# v0_6.net
KiCad netlist of a schematic drawn in EAGLE
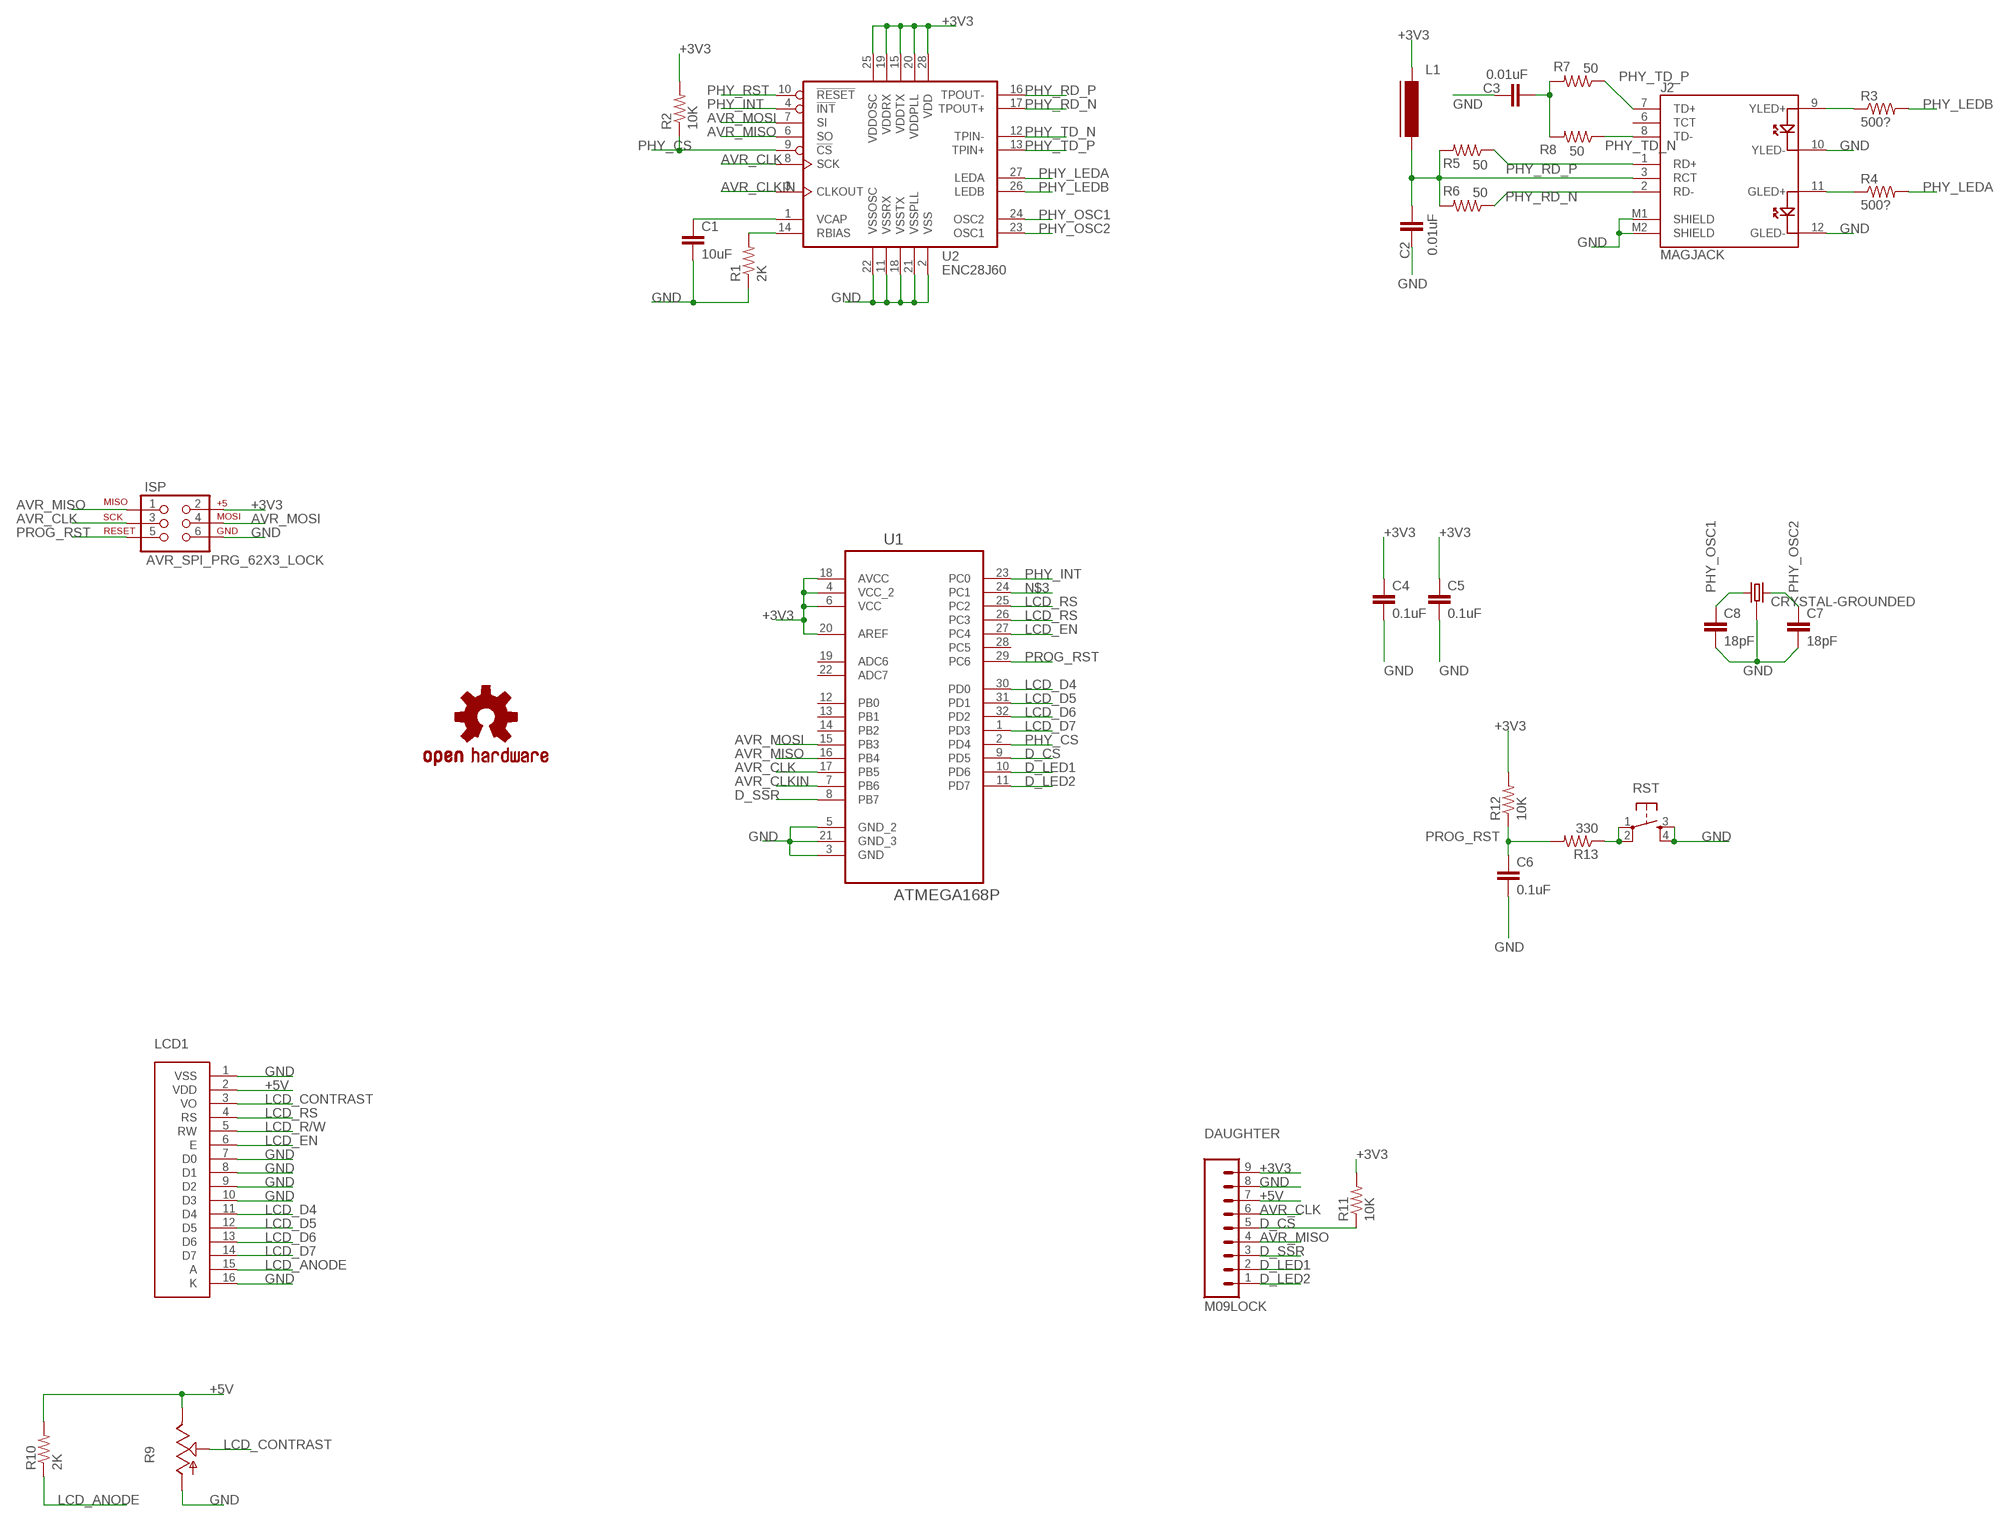
[diagram p0: schematic, sheet 1]

(export (version "E")
  (design (tool "Eeschema 10.0.6"))
  (components
    (comp (ref "C1")
      (value "10uF")
      (footprint "eagle-import:0603-CAP")
      (libsource (lib "eagle-import") (part "10UF-6.3V-20%(0603)"))
    )
    (comp (ref "C2")
      (value "0.01uF")
      (footprint "eagle-import:0603-CAP")
      (libsource (lib "eagle-import") (part "CAP0603-CAP"))
    )
    (comp (ref "C3")
      (value "0.01uF")
      (footprint "eagle-import:0603-CAP")
      (libsource (lib "eagle-import") (part "CAP0603-CAP"))
    )
    (comp (ref "C4")
      (value "0.1uF")
      (footprint "eagle-import:0402-CAP")
      (libsource (lib "eagle-import") (part "CAP0402-CAP"))
    )
    (comp (ref "C5")
      (value "0.1uF")
      (footprint "eagle-import:0402-CAP")
      (libsource (lib "eagle-import") (part "CAP0402-CAP"))
    )
    (comp (ref "C6")
      (value "0.1uF")
      (footprint "eagle-import:0603-CAP")
      (libsource (lib "eagle-import") (part "CAP0603-CAP"))
    )
    (comp (ref "C7")
      (value "18pF")
      (footprint "eagle-import:0402-CAP")
      (libsource (lib "eagle-import") (part "CAP0402-CAP"))
    )
    (comp (ref "C8")
      (value "18pF")
      (footprint "eagle-import:0402-CAP")
      (libsource (lib "eagle-import") (part "CAP0402-CAP"))
    )
    (comp (ref "DAUGHTER")
      (value "M09LOCK")
      (footprint "eagle-import:1X09_LOCK")
      (libsource (lib "eagle-import") (part "M09LOCK"))
    )
    (comp (ref "ISP")
      (value "AVR_SPI_PRG_62X3_LOCK")
      (footprint "eagle-import:2X3_LOCK")
      (libsource (lib "eagle-import") (part "AVR_SPI_PRG_62X3_LOCK"))
    )
    (comp (ref "J2")
      (value "MAGJACK")
      (footprint "eagle-import:MAGJACK")
      (libsource (lib "eagle-import") (part "MAGJACK"))
    )
    (comp (ref "L1")
      (value "FERRITE-0603")
      (footprint "eagle-import:FB603")
      (libsource (lib "eagle-import") (part "FERRITE-0603"))
    )
    (comp (ref "LCD1")
      (value "HD44780")
      (footprint "eagle-import:.1_16PIN")
      (libsource (lib "eagle-import") (part "HD44780"))
    )
    (comp (ref "LOGO1")
      (value "OSHW-LOGOS")
      (footprint "eagle-import:OSHW-LOGO-S")
      (libsource (lib "eagle-import") (part "OSHW-LOGOS"))
    )
    (comp (ref "R1")
      (value "2K")
      (footprint "eagle-import:0603-RES")
      (libsource (lib "eagle-import") (part "RESISTOR0603-RES"))
    )
    (comp (ref "R2")
      (value "10K")
      (footprint "eagle-import:0603-RES")
      (libsource (lib "eagle-import") (part "RESISTOR0603-RES"))
    )
    (comp (ref "R3")
      (value "500?")
      (footprint "eagle-import:0603-RES")
      (libsource (lib "eagle-import") (part "RESISTOR0603-RES"))
    )
    (comp (ref "R4")
      (value "500?")
      (footprint "eagle-import:0603-RES")
      (libsource (lib "eagle-import") (part "RESISTOR0603-RES"))
    )
    (comp (ref "R5")
      (value "50")
      (footprint "eagle-import:0603-RES")
      (libsource (lib "eagle-import") (part "RESISTOR0603-RES"))
    )
    (comp (ref "R6")
      (value "50")
      (footprint "eagle-import:0603-RES")
      (libsource (lib "eagle-import") (part "RESISTOR0603-RES"))
    )
    (comp (ref "R7")
      (value "50")
      (footprint "eagle-import:0603-RES")
      (libsource (lib "eagle-import") (part "RESISTOR0603-RES"))
    )
    (comp (ref "R8")
      (value "50")
      (footprint "eagle-import:0603-RES")
      (libsource (lib "eagle-import") (part "RESISTOR0603-RES"))
    )
    (comp (ref "R9")
      (value "TRIM_US-B64Y")
      (footprint "eagle-import:B64Y")
      (libsource (lib "eagle-import") (part "TRIM_US-B64Y"))
    )
    (comp (ref "R10")
      (value "2K")
      (footprint "eagle-import:0603-RES")
      (libsource (lib "eagle-import") (part "RESISTOR0603-RES"))
    )
    (comp (ref "R11")
      (value "10K")
      (footprint "eagle-import:0603-RES")
      (libsource (lib "eagle-import") (part "RESISTOR0603-RES"))
    )
    (comp (ref "R12")
      (value "10K")
      (footprint "eagle-import:0603-RES")
      (libsource (lib "eagle-import") (part "RESISTOR0603-RES"))
    )
    (comp (ref "R13")
      (value "330")
      (footprint "eagle-import:0603-RES")
      (libsource (lib "eagle-import") (part "RESISTOR0603-RES"))
    )
    (comp (ref "RST")
      (value "TAC_SWITCHSMD")
      (footprint "eagle-import:TACTILE-SWITCH-SMD")
      (libsource (lib "eagle-import") (part "TAC_SWITCHSMD"))
    )
    (comp (ref "U1")
      (value "ATMEGA168P")
      (footprint "eagle-import:QFP80P900X900X120-32N")
      (fields (field (name "MPN") "ATMEGA168P-20AU"))
      (libsource (lib "eagle-import") (part "ATMEGA168P-20AU"))
    )
    (comp (ref "U2")
      (value "ENC28J60")
      (footprint "eagle-import:SOIC-28W")
      (libsource (lib "eagle-import") (part "IC_ENC28J60-SOIC-28"))
    )
    (comp (ref "Y1")
      (value "CRYSTAL-GROUNDED")
      (footprint "eagle-import:CRYSTAL-SMD-5X3")
      (libsource (lib "eagle-import") (part "CRYSTAL-GROUNDED"))
    )
  )
  (nets
    (net (code "1") (name "/+3V3") (class "Default")
      (node (ref "C4") (pin "1") (pinfunction "1_1") (pintype "passive"))
      (node (ref "C5") (pin "1") (pinfunction "1_1") (pintype "passive"))
      (node (ref "DAUGHTER") (pin "9") (pinfunction "9_9") (pintype "passive"))
      (node (ref "ISP") (pin "2") (pinfunction "2_2") (pintype "passive"))
      (node (ref "L1") (pin "1") (pinfunction "1_1") (pintype "passive"))
      (node (ref "R11") (pin "2") (pinfunction "2_2") (pintype "passive"))
      (node (ref "R12") (pin "2") (pinfunction "2_2") (pintype "passive"))
      (node (ref "R2") (pin "2") (pinfunction "2_2") (pintype "passive"))
      (node (ref "U1") (pin "18") (pinfunction "AVCC_18") (pintype "power_in"))
      (node (ref "U1") (pin "20") (pinfunction "AREF_20") (pintype "input"))
      (node (ref "U1") (pin "4") (pinfunction "VCC_2_4") (pintype "power_in"))
      (node (ref "U1") (pin "6") (pinfunction "VCC_6") (pintype "power_in"))
      (node (ref "U2") (pin "15") (pinfunction "VDDTX_15") (pintype "power_in"))
      (node (ref "U2") (pin "19") (pinfunction "VDDRX_19") (pintype "power_in"))
      (node (ref "U2") (pin "20") (pinfunction "VDDPLL_20") (pintype "power_in"))
      (node (ref "U2") (pin "25") (pinfunction "VDDOSC_25") (pintype "power_in"))
      (node (ref "U2") (pin "28") (pinfunction "VDD_28") (pintype "power_in"))
    )
    (net (code "2") (name "/+5V") (class "Default")
      (node (ref "DAUGHTER") (pin "7") (pinfunction "7_7") (pintype "passive"))
      (node (ref "LCD1") (pin "2") (pinfunction "VDD_2") (pintype "bidirectional"))
      (node (ref "R10") (pin "2") (pinfunction "2_2") (pintype "passive"))
      (node (ref "R9") (pin "E") (pinfunction "E_E") (pintype "passive"))
    )
    (net (code "3") (name "/AVR_CLK") (class "Default")
      (node (ref "DAUGHTER") (pin "6") (pinfunction "6_6") (pintype "passive"))
      (node (ref "ISP") (pin "3") (pinfunction "3_3") (pintype "passive"))
      (node (ref "U1") (pin "17") (pinfunction "PB5_17") (pintype "bidirectional"))
      (node (ref "U2") (pin "8") (pinfunction "SCK_8") (pintype "input"))
    )
    (net (code "4") (name "/AVR_CLKIN") (class "Default")
      (node (ref "U1") (pin "7") (pinfunction "PB6_7") (pintype "bidirectional"))
      (node (ref "U2") (pin "3") (pinfunction "CLKOUT_3") (pintype "output"))
    )
    (net (code "5") (name "/AVR_MISO") (class "Default")
      (node (ref "DAUGHTER") (pin "4") (pinfunction "4_4") (pintype "passive"))
      (node (ref "ISP") (pin "1") (pinfunction "1_1") (pintype "passive"))
      (node (ref "U1") (pin "16") (pinfunction "PB4_16") (pintype "bidirectional"))
      (node (ref "U2") (pin "6") (pinfunction "SO_6") (pintype "output"))
    )
    (net (code "6") (name "/AVR_MOSI") (class "Default")
      (node (ref "ISP") (pin "4") (pinfunction "4_4") (pintype "passive"))
      (node (ref "U1") (pin "15") (pinfunction "PB3_15") (pintype "bidirectional"))
      (node (ref "U2") (pin "7") (pinfunction "SI_7") (pintype "input"))
    )
    (net (code "7") (name "/D_CS") (class "Default")
      (node (ref "DAUGHTER") (pin "5") (pinfunction "5_5") (pintype "passive"))
      (node (ref "R11") (pin "1") (pinfunction "1_1") (pintype "passive"))
      (node (ref "U1") (pin "9") (pinfunction "PD5_9") (pintype "bidirectional"))
    )
    (net (code "8") (name "/D_LED1") (class "Default")
      (node (ref "DAUGHTER") (pin "2") (pinfunction "2_2") (pintype "passive"))
      (node (ref "U1") (pin "10") (pinfunction "PD6_10") (pintype "bidirectional"))
    )
    (net (code "9") (name "/D_LED2") (class "Default")
      (node (ref "DAUGHTER") (pin "1") (pinfunction "1_1") (pintype "passive"))
      (node (ref "U1") (pin "11") (pinfunction "PD7_11") (pintype "bidirectional"))
    )
    (net (code "10") (name "/D_SSR") (class "Default")
      (node (ref "DAUGHTER") (pin "3") (pinfunction "3_3") (pintype "passive"))
      (node (ref "U1") (pin "8") (pinfunction "PB7_8") (pintype "bidirectional"))
    )
    (net (code "11") (name "/GND") (class "Default")
      (node (ref "C1") (pin "2") (pinfunction "2_2") (pintype "passive"))
      (node (ref "C2") (pin "1") (pinfunction "1_1") (pintype "passive"))
      (node (ref "C3") (pin "1") (pinfunction "1_1") (pintype "passive"))
      (node (ref "C4") (pin "2") (pinfunction "2_2") (pintype "passive"))
      (node (ref "C5") (pin "2") (pinfunction "2_2") (pintype "passive"))
      (node (ref "C6") (pin "2") (pinfunction "2_2") (pintype "passive"))
      (node (ref "C7") (pin "2") (pinfunction "2_2") (pintype "passive"))
      (node (ref "C8") (pin "2") (pinfunction "2_2") (pintype "passive"))
      (node (ref "DAUGHTER") (pin "8") (pinfunction "8_8") (pintype "passive"))
      (node (ref "ISP") (pin "6") (pinfunction "6_6") (pintype "passive"))
      (node (ref "J2") (pin "10") (pinfunction "YLED-_10") (pintype "bidirectional"))
      (node (ref "J2") (pin "12") (pinfunction "GLED-_12") (pintype "bidirectional"))
      (node (ref "J2") (pin "M1") (pinfunction "SHIELD_M1") (pintype "bidirectional"))
      (node (ref "J2") (pin "M2") (pinfunction "SHIELD_M2") (pintype "bidirectional"))
      (node (ref "LCD1") (pin "1") (pinfunction "VSS_1") (pintype "bidirectional"))
      (node (ref "LCD1") (pin "10") (pinfunction "D3_10") (pintype "bidirectional"))
      (node (ref "LCD1") (pin "16") (pinfunction "K_16") (pintype "bidirectional"))
      (node (ref "LCD1") (pin "7") (pinfunction "D0_7") (pintype "bidirectional"))
      (node (ref "LCD1") (pin "8") (pinfunction "D1_8") (pintype "bidirectional"))
      (node (ref "LCD1") (pin "9") (pinfunction "D2_9") (pintype "bidirectional"))
      (node (ref "R1") (pin "1") (pinfunction "1_1") (pintype "passive"))
      (node (ref "R9") (pin "A") (pinfunction "A_A") (pintype "passive"))
      (node (ref "RST") (pin "3") (pinfunction "3_3") (pintype "passive"))
      (node (ref "RST") (pin "4") (pinfunction "4_4") (pintype "passive"))
      (node (ref "U1") (pin "21") (pinfunction "GND_3_21") (pintype "passive"))
      (node (ref "U1") (pin "3") (pinfunction "GND_3") (pintype "passive"))
      (node (ref "U1") (pin "5") (pinfunction "GND_2_5") (pintype "passive"))
      (node (ref "U2") (pin "11") (pinfunction "VSSRX_11") (pintype "power_in"))
      (node (ref "U2") (pin "18") (pinfunction "VSSTX_18") (pintype "power_in"))
      (node (ref "U2") (pin "2") (pinfunction "VSS_2") (pintype "power_in"))
      (node (ref "U2") (pin "21") (pinfunction "VSSPLL_21") (pintype "power_in"))
      (node (ref "U2") (pin "22") (pinfunction "VSSOSC_22") (pintype "power_in"))
      (node (ref "Y1") (pin "2") (pinfunction "3_2") (pintype "passive"))
      (node (ref "Y1") (pin "4") (pinfunction "3_4") (pintype "passive"))
    )
    (net (code "12") (name "/LCD_ANODE") (class "Default")
      (node (ref "LCD1") (pin "15") (pinfunction "A_15") (pintype "bidirectional"))
      (node (ref "R10") (pin "1") (pinfunction "1_1") (pintype "passive"))
    )
    (net (code "13") (name "/LCD_CONTRAST") (class "Default")
      (node (ref "LCD1") (pin "3") (pinfunction "VO_3") (pintype "bidirectional"))
      (node (ref "R9") (pin "S") (pinfunction "S_S") (pintype "passive"))
    )
    (net (code "14") (name "/LCD_D4") (class "Default")
      (node (ref "LCD1") (pin "11") (pinfunction "D4_11") (pintype "bidirectional"))
      (node (ref "U1") (pin "30") (pinfunction "PD0_30") (pintype "bidirectional"))
    )
    (net (code "15") (name "/LCD_D5") (class "Default")
      (node (ref "LCD1") (pin "12") (pinfunction "D5_12") (pintype "bidirectional"))
      (node (ref "U1") (pin "31") (pinfunction "PD1_31") (pintype "bidirectional"))
    )
    (net (code "16") (name "/LCD_D6") (class "Default")
      (node (ref "LCD1") (pin "13") (pinfunction "D6_13") (pintype "bidirectional"))
      (node (ref "U1") (pin "32") (pinfunction "PD2_32") (pintype "bidirectional"))
    )
    (net (code "17") (name "/LCD_D7") (class "Default")
      (node (ref "LCD1") (pin "14") (pinfunction "D7_14") (pintype "bidirectional"))
      (node (ref "U1") (pin "1") (pinfunction "PD3_1") (pintype "bidirectional"))
    )
    (net (code "18") (name "/LCD_EN") (class "Default")
      (node (ref "LCD1") (pin "6") (pinfunction "E_6") (pintype "bidirectional"))
      (node (ref "U1") (pin "27") (pinfunction "PC4_27") (pintype "bidirectional"))
    )
    (net (code "19") (name "/LCD_RS") (class "Default")
      (node (ref "LCD1") (pin "4") (pinfunction "RS_4") (pintype "bidirectional"))
      (node (ref "U1") (pin "25") (pinfunction "PC2_25") (pintype "bidirectional"))
    )
    (net (code "20") (name "/LCD_R{slash}W") (class "Default")
      (node (ref "LCD1") (pin "5") (pinfunction "RW_5") (pintype "bidirectional"))
      (node (ref "U1") (pin "26") (pinfunction "PC3_26") (pintype "bidirectional"))
    )
    (net (code "21") (name "/N$3") (class "Default")
      (node (ref "U1") (pin "24") (pinfunction "PC1_24") (pintype "bidirectional"))
    )
    (net (code "22") (name "/PHY_CS") (class "Default")
      (node (ref "R2") (pin "1") (pinfunction "1_1") (pintype "passive"))
      (node (ref "U1") (pin "2") (pinfunction "PD4_2") (pintype "bidirectional"))
      (node (ref "U2") (pin "9") (pinfunction "~{CS}_9") (pintype "input"))
    )
    (net (code "23") (name "/PHY_INT") (class "Default")
      (node (ref "U1") (pin "23") (pinfunction "PC0_23") (pintype "bidirectional"))
      (node (ref "U2") (pin "4") (pinfunction "~{INT}_4") (pintype "output"))
    )
    (net (code "24") (name "/PHY_LEDA") (class "Default")
      (node (ref "R4") (pin "2") (pinfunction "2_2") (pintype "passive"))
      (node (ref "U2") (pin "27") (pinfunction "LEDA_27") (pintype "output"))
    )
    (net (code "25") (name "/PHY_LEDB") (class "Default")
      (node (ref "R3") (pin "2") (pinfunction "2_2") (pintype "passive"))
      (node (ref "U2") (pin "26") (pinfunction "LEDB_26") (pintype "output"))
    )
    (net (code "26") (name "/PHY_OSC1") (class "Default")
      (node (ref "C8") (pin "1") (pinfunction "1_1") (pintype "passive"))
      (node (ref "U2") (pin "24") (pinfunction "OSC2_24") (pintype "output"))
      (node (ref "Y1") (pin "3") (pinfunction "1_3") (pintype "passive"))
    )
    (net (code "27") (name "/PHY_OSC2") (class "Default")
      (node (ref "C7") (pin "1") (pinfunction "1_1") (pintype "passive"))
      (node (ref "U2") (pin "23") (pinfunction "OSC1_23") (pintype "input"))
      (node (ref "Y1") (pin "1") (pinfunction "2_1") (pintype "passive"))
    )
    (net (code "28") (name "/PHY_RD_N") (class "Default")
      (node (ref "J2") (pin "2") (pinfunction "RD-_2") (pintype "bidirectional"))
      (node (ref "R6") (pin "1") (pinfunction "1_1") (pintype "passive"))
      (node (ref "U2") (pin "17") (pinfunction "TPOUT+_17") (pintype "output"))
    )
    (net (code "29") (name "/PHY_RD_P") (class "Default")
      (node (ref "J2") (pin "1") (pinfunction "RD+_1") (pintype "bidirectional"))
      (node (ref "R5") (pin "1") (pinfunction "1_1") (pintype "passive"))
      (node (ref "U2") (pin "16") (pinfunction "TPOUT-_16") (pintype "output"))
    )
    (net (code "30") (name "/PHY_RST") (class "Default")
      (node (ref "U2") (pin "10") (pinfunction "~{RESET}_10") (pintype "input"))
    )
    (net (code "31") (name "/PHY_TD_N") (class "Default")
      (node (ref "J2") (pin "8") (pinfunction "TD-_8") (pintype "bidirectional"))
      (node (ref "R8") (pin "1") (pinfunction "1_1") (pintype "passive"))
      (node (ref "U2") (pin "12") (pinfunction "TPIN-_12") (pintype "input"))
    )
    (net (code "32") (name "/PHY_TD_P") (class "Default")
      (node (ref "J2") (pin "7") (pinfunction "TD+_7") (pintype "bidirectional"))
      (node (ref "R7") (pin "1") (pinfunction "1_1") (pintype "passive"))
      (node (ref "U2") (pin "13") (pinfunction "TPIN+_13") (pintype "input"))
    )
    (net (code "33") (name "/PROG_RST") (class "Default")
      (node (ref "C6") (pin "1") (pinfunction "1_1") (pintype "passive"))
      (node (ref "ISP") (pin "5") (pinfunction "5_5") (pintype "passive"))
      (node (ref "R12") (pin "1") (pinfunction "1_1") (pintype "passive"))
      (node (ref "R13") (pin "2") (pinfunction "2_2") (pintype "passive"))
      (node (ref "U1") (pin "29") (pinfunction "PC6_29") (pintype "bidirectional"))
    )
    (net (code "34") (name "Net-(C3-Pad2)") (class "Default")
      (node (ref "C3") (pin "2") (pinfunction "2_2") (pintype "passive"))
      (node (ref "R7") (pin "2") (pinfunction "2_2") (pintype "passive"))
      (node (ref "R8") (pin "2") (pinfunction "2_2") (pintype "passive"))
    )
    (net (code "35") (name "Net-(J2-GLED+)") (class "Default")
      (node (ref "J2") (pin "11") (pinfunction "GLED+_11") (pintype "bidirectional"))
      (node (ref "R4") (pin "1") (pinfunction "1_1") (pintype "passive"))
    )
    (net (code "36") (name "Net-(J2-RCT)") (class "Default")
      (node (ref "C2") (pin "2") (pinfunction "2_2") (pintype "passive"))
      (node (ref "J2") (pin "3") (pinfunction "RCT_3") (pintype "bidirectional"))
      (node (ref "L1") (pin "2") (pinfunction "2_2") (pintype "passive"))
      (node (ref "R5") (pin "2") (pinfunction "2_2") (pintype "passive"))
      (node (ref "R6") (pin "2") (pinfunction "2_2") (pintype "passive"))
    )
    (net (code "37") (name "Net-(J2-YLED+)") (class "Default")
      (node (ref "J2") (pin "9") (pinfunction "YLED+_9") (pintype "bidirectional"))
      (node (ref "R3") (pin "1") (pinfunction "1_1") (pintype "passive"))
    )
    (net (code "38") (name "Net-(R13-Pad1)") (class "Default")
      (node (ref "R13") (pin "1") (pinfunction "1_1") (pintype "passive"))
      (node (ref "RST") (pin "1") (pinfunction "1_1") (pintype "passive"))
      (node (ref "RST") (pin "2") (pinfunction "2_2") (pintype "passive"))
    )
    (net (code "39") (name "Net-(U2-RBIAS)") (class "Default")
      (node (ref "R1") (pin "2") (pinfunction "2_2") (pintype "passive"))
      (node (ref "U2") (pin "14") (pinfunction "RBIAS_14") (pintype "input"))
    )
    (net (code "40") (name "Net-(U2-VCAP)") (class "Default")
      (node (ref "C1") (pin "1") (pinfunction "1_1") (pintype "passive"))
      (node (ref "U2") (pin "1") (pinfunction "VCAP_1") (pintype "input"))
    )
    (net (code "41") (name "unconnected-(J2-TCT-Pad6)") (class "Default")
      (node (ref "J2") (pin "6") (pinfunction "TCT_6") (pintype "bidirectional"))
    )
    (net (code "42") (name "unconnected-(U1-ADC6-Pad19)") (class "Default")
      (node (ref "U1") (pin "19") (pinfunction "ADC6_19") (pintype "input"))
    )
    (net (code "43") (name "unconnected-(U1-ADC7-Pad22)") (class "Default")
      (node (ref "U1") (pin "22") (pinfunction "ADC7_22") (pintype "input"))
    )
    (net (code "44") (name "unconnected-(U1-PB0-Pad12)") (class "Default")
      (node (ref "U1") (pin "12") (pinfunction "PB0_12") (pintype "bidirectional"))
    )
    (net (code "45") (name "unconnected-(U1-PB1-Pad13)") (class "Default")
      (node (ref "U1") (pin "13") (pinfunction "PB1_13") (pintype "bidirectional"))
    )
    (net (code "46") (name "unconnected-(U1-PB2-Pad14)") (class "Default")
      (node (ref "U1") (pin "14") (pinfunction "PB2_14") (pintype "bidirectional"))
    )
    (net (code "47") (name "unconnected-(U1-PC5-Pad28)") (class "Default")
      (node (ref "U1") (pin "28") (pinfunction "PC5_28") (pintype "bidirectional"))
    )
  )
)
